# Sheet12.net
KiCad netlist of a schematic drawn in Altium Designer
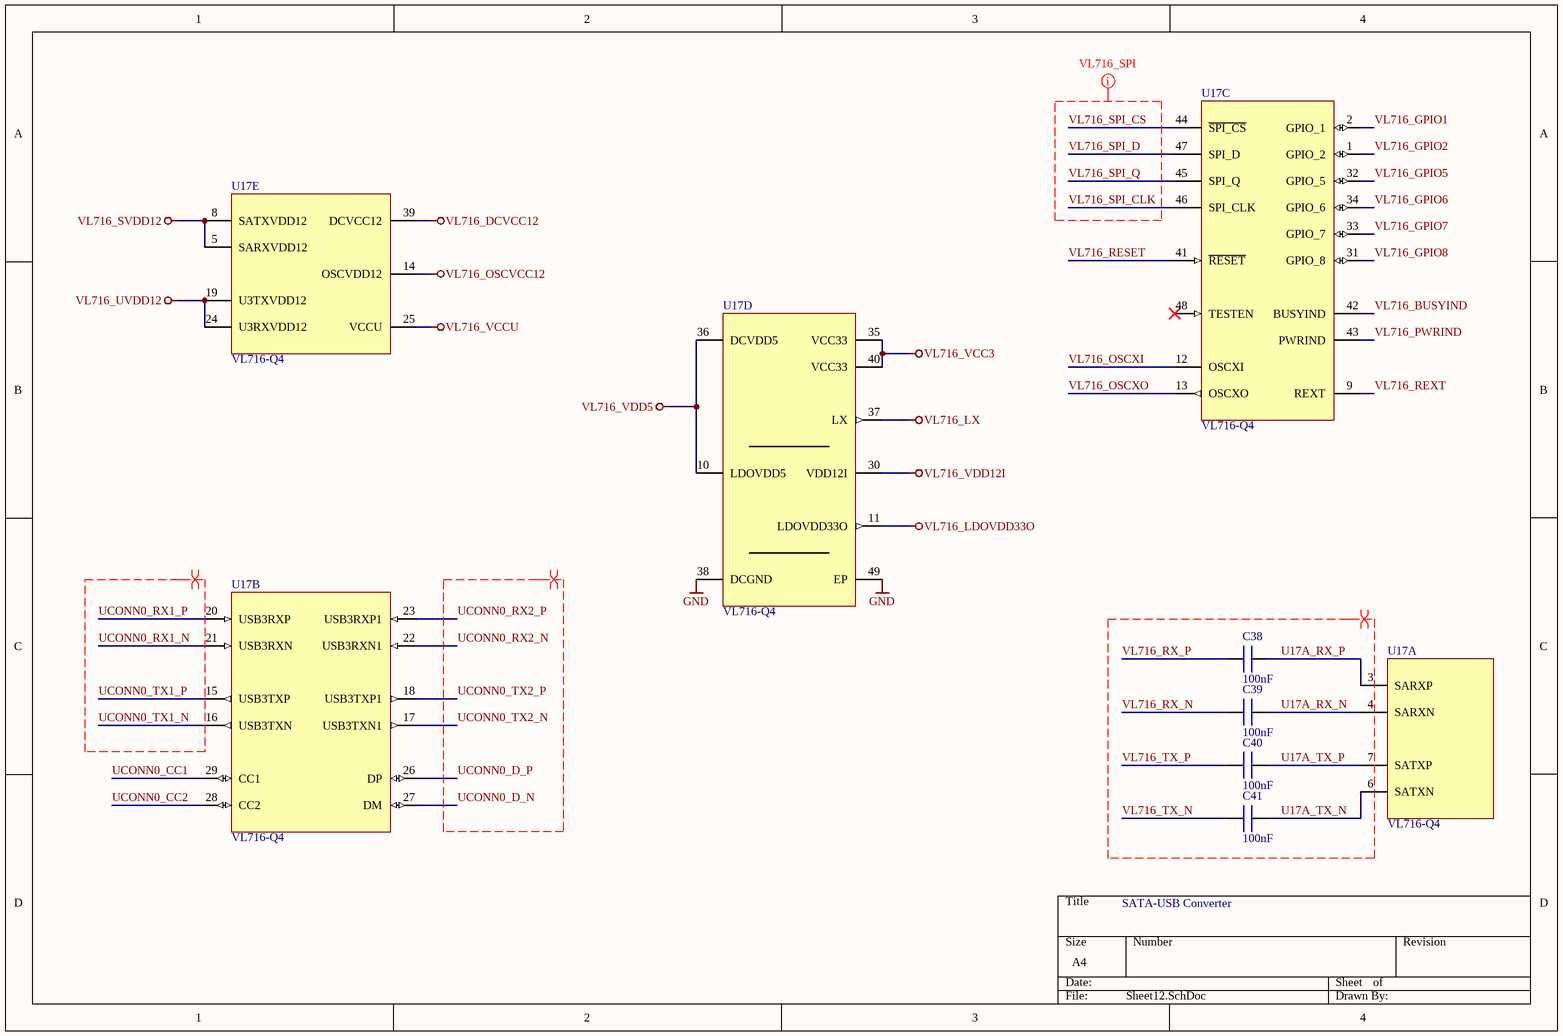
[diagram p0: Sheet12.SchDoc]

(export (version "E")
  (design (tool "Eeschema 10.0.6"))
  (components
    (comp (ref "C38")
      (value "100nF")
      (footprint "CAPC1005X05N")
      (description "Ceramic Chip Capacitor")
      (libsource (lib "Integrated_Library") (part "C0402"))
    )
    (comp (ref "C39")
      (value "100nF")
      (footprint "CAPC1005X05N")
      (description "Ceramic Chip Capacitor")
      (libsource (lib "Integrated_Library") (part "C0402"))
    )
    (comp (ref "C40")
      (value "100nF")
      (footprint "CAPC1005X05N")
      (description "Ceramic Chip Capacitor")
      (libsource (lib "Integrated_Library") (part "C0402"))
    )
    (comp (ref "C41")
      (value "100nF")
      (footprint "CAPC1005X05N")
      (description "Ceramic Chip Capacitor")
      (libsource (lib "Integrated_Library") (part "C0402"))
    )
    (comp (ref "U17")
      (value "VL716-Q4")
      (footprint "VL716-Q4")
      (description "USB 3.1 to SATA 6Gb/s bridge controller with USB type-C connector support")
      (libsource (lib "Integrated_Library") (part "VL716-Q4"))
    )
  )
  (nets
    (net (code "1") (name "/U17A_RX_N") (class "Default")
      (node (ref "C39") (pin "1") (pinfunction "1_1") (pintype "passive"))
      (node (ref "U17") (pin "4") (pinfunction "SARXN_4") (pintype "input"))
    )
    (net (code "2") (name "/U17A_RX_P") (class "Default")
      (node (ref "C38") (pin "1") (pinfunction "1_1") (pintype "passive"))
      (node (ref "U17") (pin "3") (pinfunction "SARXP_3") (pintype "input"))
    )
    (net (code "3") (name "/U17A_TX_N") (class "Default")
      (node (ref "C41") (pin "1") (pinfunction "1_1") (pintype "passive"))
      (node (ref "U17") (pin "6") (pinfunction "SATXN_6") (pintype "output"))
    )
    (net (code "4") (name "/U17A_TX_P") (class "Default")
      (node (ref "C40") (pin "1") (pinfunction "1_1") (pintype "passive"))
      (node (ref "U17") (pin "7") (pinfunction "SATXP_7") (pintype "output"))
    )
    (net (code "5") (name "/UCONN0_CC1") (class "Default")
      (node (ref "U17") (pin "29") (pinfunction "CC1_29") (pintype "bidirectional"))
    )
    (net (code "6") (name "/UCONN0_CC2") (class "Default")
      (node (ref "U17") (pin "28") (pinfunction "CC2_28") (pintype "bidirectional"))
    )
    (net (code "7") (name "/UCONN0_D_N") (class "Default")
      (node (ref "U17") (pin "27") (pinfunction "DM_27") (pintype "bidirectional"))
    )
    (net (code "8") (name "/UCONN0_D_P") (class "Default")
      (node (ref "U17") (pin "26") (pinfunction "DP_26") (pintype "bidirectional"))
    )
    (net (code "9") (name "/UCONN0_RX1_N") (class "Default")
      (node (ref "U17") (pin "21") (pinfunction "USB3RXN_21") (pintype "input"))
    )
    (net (code "10") (name "/UCONN0_RX1_P") (class "Default")
      (node (ref "U17") (pin "20") (pinfunction "USB3RXP_20") (pintype "input"))
    )
    (net (code "11") (name "/UCONN0_RX2_N") (class "Default")
      (node (ref "U17") (pin "22") (pinfunction "USB3RXN1_22") (pintype "input"))
    )
    (net (code "12") (name "/UCONN0_RX2_P") (class "Default")
      (node (ref "U17") (pin "23") (pinfunction "USB3RXP1_23") (pintype "input"))
    )
    (net (code "13") (name "/UCONN0_TX1_N") (class "Default")
      (node (ref "U17") (pin "16") (pinfunction "USB3TXN_16") (pintype "output"))
    )
    (net (code "14") (name "/UCONN0_TX1_P") (class "Default")
      (node (ref "U17") (pin "15") (pinfunction "USB3TXP_15") (pintype "output"))
    )
    (net (code "15") (name "/UCONN0_TX2_N") (class "Default")
      (node (ref "U17") (pin "17") (pinfunction "USB3TXN1_17") (pintype "output"))
    )
    (net (code "16") (name "/UCONN0_TX2_P") (class "Default")
      (node (ref "U17") (pin "18") (pinfunction "USB3TXP1_18") (pintype "output"))
    )
    (net (code "17") (name "/VL716_BUSYIND") (class "Default")
      (node (ref "U17") (pin "42") (pinfunction "BUSYIND_42") (pintype "output"))
    )
    (net (code "18") (name "/VL716_GPIO1") (class "Default")
      (node (ref "U17") (pin "2") (pinfunction "GPIO_1_2") (pintype "bidirectional"))
    )
    (net (code "19") (name "/VL716_GPIO2") (class "Default")
      (node (ref "U17") (pin "1") (pinfunction "GPIO_2_1") (pintype "bidirectional"))
    )
    (net (code "20") (name "/VL716_GPIO5") (class "Default")
      (node (ref "U17") (pin "32") (pinfunction "GPIO_5_32") (pintype "bidirectional"))
    )
    (net (code "21") (name "/VL716_GPIO6") (class "Default")
      (node (ref "U17") (pin "34") (pinfunction "GPIO_6_34") (pintype "bidirectional"))
    )
    (net (code "22") (name "/VL716_GPIO7") (class "Default")
      (node (ref "U17") (pin "33") (pinfunction "GPIO_7_33") (pintype "bidirectional"))
    )
    (net (code "23") (name "/VL716_GPIO8") (class "Default")
      (node (ref "U17") (pin "31") (pinfunction "GPIO_8_31") (pintype "bidirectional"))
    )
    (net (code "24") (name "/VL716_OSCXI") (class "Default")
      (node (ref "U17") (pin "12") (pinfunction "OSCXI_12") (pintype "input"))
    )
    (net (code "25") (name "/VL716_OSCXO") (class "Default")
      (node (ref "U17") (pin "13") (pinfunction "OSCXO_13") (pintype "output"))
    )
    (net (code "26") (name "/VL716_PWRIND") (class "Default")
      (node (ref "U17") (pin "43") (pinfunction "PWRIND_43") (pintype "output"))
    )
    (net (code "27") (name "/VL716_RESET") (class "Default")
      (node (ref "U17") (pin "41") (pinfunction "~{RESET}_41") (pintype "input"))
    )
    (net (code "28") (name "/VL716_REXT") (class "Default")
      (node (ref "U17") (pin "9") (pinfunction "REXT_9") (pintype "passive"))
    )
    (net (code "29") (name "/VL716_RX_N") (class "Default")
      (node (ref "C39") (pin "2") (pinfunction "2_2") (pintype "passive"))
    )
    (net (code "30") (name "/VL716_RX_P") (class "Default")
      (node (ref "C38") (pin "2") (pinfunction "2_2") (pintype "passive"))
    )
    (net (code "31") (name "/VL716_SPI_CLK") (class "Default")
      (node (ref "U17") (pin "46") (pinfunction "SPI_CLK_46") (pintype "output"))
    )
    (net (code "32") (name "/VL716_SPI_CS") (class "Default")
      (node (ref "U17") (pin "44") (pinfunction "~{SPI_CS}_44") (pintype "output"))
    )
    (net (code "33") (name "/VL716_SPI_D") (class "Default")
      (node (ref "U17") (pin "47") (pinfunction "SPI_D_47") (pintype "output"))
    )
    (net (code "34") (name "/VL716_SPI_Q") (class "Default")
      (node (ref "U17") (pin "45") (pinfunction "SPI_Q_45") (pintype "input"))
    )
    (net (code "35") (name "/VL716_TX_N") (class "Default")
      (node (ref "C41") (pin "2") (pinfunction "2_2") (pintype "passive"))
    )
    (net (code "36") (name "/VL716_TX_P") (class "Default")
      (node (ref "C40") (pin "2") (pinfunction "2_2") (pintype "passive"))
    )
    (net (code "37") (name "GND") (class "Default")
      (node (ref "U17") (pin "38") (pinfunction "DCGND_38") (pintype "power_in"))
      (node (ref "U17") (pin "49") (pinfunction "EP_49") (pintype "power_in"))
    )
    (net (code "38") (name "VL716_DCVCC12") (class "Default")
      (node (ref "U17") (pin "39") (pinfunction "DCVCC12_39") (pintype "power_in"))
    )
    (net (code "39") (name "VL716_LDOVDD33O") (class "Default")
      (node (ref "U17") (pin "11") (pinfunction "LDOVDD33O_11") (pintype "output"))
    )
    (net (code "40") (name "VL716_LX") (class "Default")
      (node (ref "U17") (pin "37") (pinfunction "LX_37") (pintype "output"))
    )
    (net (code "41") (name "VL716_OSCVCC12") (class "Default")
      (node (ref "U17") (pin "14") (pinfunction "OSCVDD12_14") (pintype "power_in"))
    )
    (net (code "42") (name "VL716_SVDD12") (class "Default")
      (node (ref "U17") (pin "5") (pinfunction "SARXVDD12_5") (pintype "power_in"))
      (node (ref "U17") (pin "8") (pinfunction "SATXVDD12_8") (pintype "power_in"))
    )
    (net (code "43") (name "VL716_UVDD12") (class "Default")
      (node (ref "U17") (pin "19") (pinfunction "U3TXVDD12_19") (pintype "power_in"))
      (node (ref "U17") (pin "24") (pinfunction "U3RXVDD12_24") (pintype "power_in"))
    )
    (net (code "44") (name "VL716_VCC3") (class "Default")
      (node (ref "U17") (pin "35") (pinfunction "VCC33_35") (pintype "power_in"))
      (node (ref "U17") (pin "40") (pinfunction "VCC33_40") (pintype "power_in"))
    )
    (net (code "45") (name "VL716_VCCU") (class "Default")
      (node (ref "U17") (pin "25") (pinfunction "VCCU_25") (pintype "power_in"))
    )
    (net (code "46") (name "VL716_VDD5") (class "Default")
      (node (ref "U17") (pin "10") (pinfunction "LDOVDD5_10") (pintype "power_in"))
      (node (ref "U17") (pin "36") (pinfunction "DCVDD5_36") (pintype "power_in"))
    )
    (net (code "47") (name "VL716_VDD12I") (class "Default")
      (node (ref "U17") (pin "30") (pinfunction "VDD12I_30") (pintype "power_in"))
    )
    (net (code "48") (name "unconnected-(U17C-TESTEN-Pad48)") (class "Default")
      (node (ref "U17") (pin "48") (pinfunction "TESTEN_48") (pintype "input+no_connect"))
    )
  )
)
